# GIP-SIM900.net
KiCad netlist of a schematic drawn in EAGLE
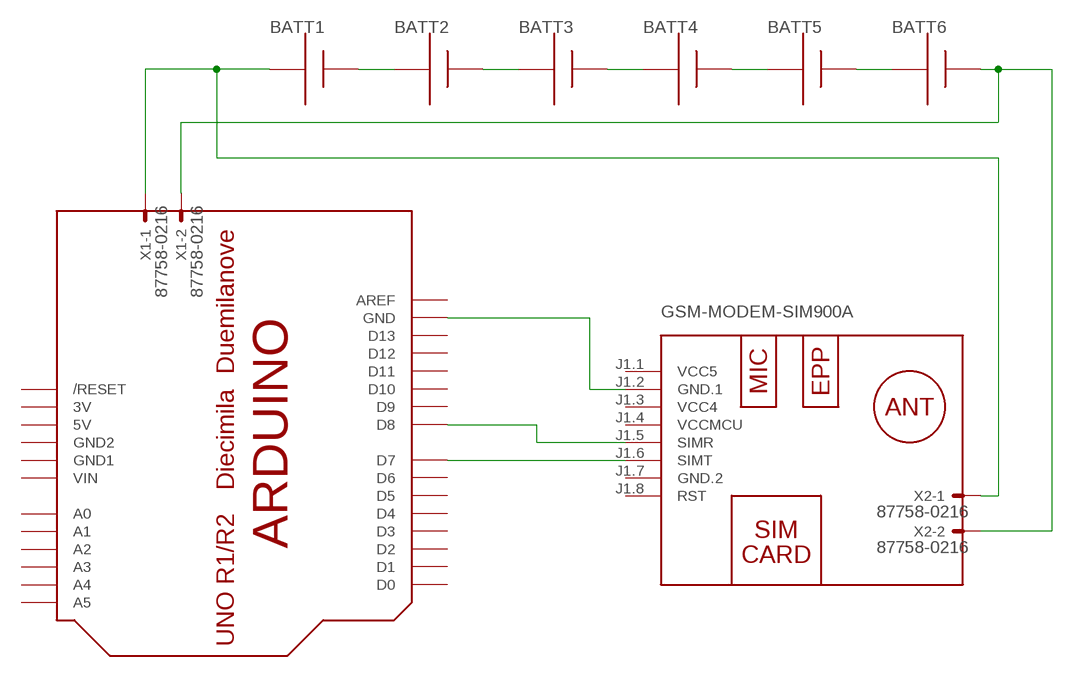
[diagram p0: schematic, sheet 1]

(export (version "E")
  (design (tool "Eeschema 10.0.6"))
  (components
    (comp (ref "BATT1")
      (value "AAA")
      (footprint "eagle-import:12BH412")
      (libsource (lib "eagle-import") (part "AAA"))
    )
    (comp (ref "BATT2")
      (value "AAA")
      (footprint "eagle-import:12BH412")
      (libsource (lib "eagle-import") (part "AAA"))
    )
    (comp (ref "BATT3")
      (value "AAA")
      (footprint "eagle-import:12BH412")
      (libsource (lib "eagle-import") (part "AAA"))
    )
    (comp (ref "BATT4")
      (value "AAA")
      (footprint "eagle-import:12BH412")
      (libsource (lib "eagle-import") (part "AAA"))
    )
    (comp (ref "BATT5")
      (value "AAA")
      (footprint "eagle-import:12BH412")
      (libsource (lib "eagle-import") (part "AAA"))
    )
    (comp (ref "BATT6")
      (value "AAA")
      (footprint "eagle-import:12BH412")
      (libsource (lib "eagle-import") (part "AAA"))
    )
    (comp (ref "U$1")
      (value "GSM-MODEM-SIM900A")
      (footprint "eagle-import:GSM-MODEM-SIM900A")
      (libsource (lib "eagle-import") (part "GSM-MODEM-SIM900A"))
    )
    (comp (ref "U$2")
      (value "ARDUINO-BPLACE")
      (footprint "eagle-import:ARDUINO-BPLACE")
      (libsource (lib "eagle-import") (part "ARDUINO-BPLACE"))
    )
    (comp (ref "X1")
      (value "87758-0216")
      (footprint "eagle-import:87758-0216")
      (fields (field (name "MF") "MOLEX"))
      (libsource (lib "eagle-import") (part "87758-0216"))
    )
    (comp (ref "X2")
      (value "87758-0216")
      (footprint "eagle-import:87758-0216")
      (fields (field (name "MF") "MOLEX"))
      (libsource (lib "eagle-import") (part "87758-0216"))
    )
  )
  (nets
    (net (code "1") (name "/3V") (class "Default")
      (node (ref "U$2") (pin "3V") (pinfunction "3V_3V") (pintype "power_in"))
    )
    (net (code "2") (name "/5V") (class "Default")
      (node (ref "U$2") (pin "5V") (pinfunction "5V_5V") (pintype "power_in"))
    )
    (net (code "3") (name "/GND.2") (class "Default")
      (node (ref "U$1") (pin "J1.7") (pinfunction "GND.2_J1.7") (pintype "power_in"))
    )
    (net (code "4") (name "/GND1") (class "Default")
      (node (ref "U$2") (pin "GND1") (pinfunction "GND1_GND1") (pintype "power_in"))
    )
    (net (code "5") (name "/GND2") (class "Default")
      (node (ref "U$2") (pin "GND2") (pinfunction "GND2_GND2") (pintype "power_in"))
    )
    (net (code "6") (name "/VCC4") (class "Default")
      (node (ref "U$1") (pin "J1.3") (pinfunction "VCC4_J1.3") (pintype "power_in"))
    )
    (net (code "7") (name "/VCC5") (class "Default")
      (node (ref "U$1") (pin "J1.1") (pinfunction "VCC5_J1.1") (pintype "power_in"))
    )
    (net (code "8") (name "/VCCMCU") (class "Default")
      (node (ref "U$1") (pin "J1.4") (pinfunction "VCCMCU_J1.4") (pintype "power_in"))
    )
    (net (code "9") (name "/VIN") (class "Default")
      (node (ref "U$2") (pin "VIN") (pinfunction "VIN_VIN") (pintype "power_in"))
    )
    (net (code "10") (name "Net-(BATT1-Pad+)") (class "Default")
      (node (ref "BATT1") (pin "+") (pinfunction "+_+") (pintype "bidirectional"))
      (node (ref "BATT2") (pin "-") (pinfunction "-_-") (pintype "bidirectional"))
    )
    (net (code "11") (name "Net-(BATT2-Pad+)") (class "Default")
      (node (ref "BATT2") (pin "+") (pinfunction "+_+") (pintype "bidirectional"))
      (node (ref "BATT3") (pin "-") (pinfunction "-_-") (pintype "bidirectional"))
    )
    (net (code "12") (name "Net-(BATT3-Pad+)") (class "Default")
      (node (ref "BATT3") (pin "+") (pinfunction "+_+") (pintype "bidirectional"))
      (node (ref "BATT4") (pin "-") (pinfunction "-_-") (pintype "bidirectional"))
    )
    (net (code "13") (name "Net-(BATT4-Pad+)") (class "Default")
      (node (ref "BATT4") (pin "+") (pinfunction "+_+") (pintype "bidirectional"))
      (node (ref "BATT5") (pin "-") (pinfunction "-_-") (pintype "bidirectional"))
    )
    (net (code "14") (name "Net-(BATT5-Pad+)") (class "Default")
      (node (ref "BATT5") (pin "+") (pinfunction "+_+") (pintype "bidirectional"))
      (node (ref "BATT6") (pin "-") (pinfunction "-_-") (pintype "bidirectional"))
    )
    (net (code "15") (name "Net-(U$1-GND.1)") (class "Default")
      (node (ref "U$1") (pin "J1.2") (pinfunction "GND.1_J1.2") (pintype "power_in"))
      (node (ref "U$2") (pin "GND") (pinfunction "GND_GND") (pintype "power_in"))
    )
    (net (code "16") (name "Net-(U$1-SIMR)") (class "Default")
      (node (ref "U$1") (pin "J1.5") (pinfunction "SIMR_J1.5") (pintype "bidirectional"))
      (node (ref "U$2") (pin "D8") (pinfunction "D8_D8") (pintype "bidirectional"))
    )
    (net (code "17") (name "Net-(U$1-SIMT)") (class "Default")
      (node (ref "U$1") (pin "J1.6") (pinfunction "SIMT_J1.6") (pintype "bidirectional"))
      (node (ref "U$2") (pin "D7") (pinfunction "D7_D7") (pintype "bidirectional"))
    )
    (net (code "18") (name "Net-(X1A-S)") (class "Default")
      (node (ref "BATT1") (pin "-") (pinfunction "-_-") (pintype "bidirectional"))
      (node (ref "X1") (pin "1") (pinfunction "S_1") (pintype "passive"))
      (node (ref "X2") (pin "1") (pinfunction "S_1") (pintype "passive"))
    )
    (net (code "19") (name "Net-(X1B-S)") (class "Default")
      (node (ref "BATT6") (pin "+") (pinfunction "+_+") (pintype "bidirectional"))
      (node (ref "X1") (pin "2") (pinfunction "S_2") (pintype "passive"))
      (node (ref "X2") (pin "2") (pinfunction "S_2") (pintype "passive"))
    )
    (net (code "20") (name "unconnected-(U$1-RST-PadJ1.8)") (class "Default")
      (node (ref "U$1") (pin "J1.8") (pinfunction "RST_J1.8") (pintype "bidirectional"))
    )
    (net (code "21") (name "unconnected-(U$2-PadA0)") (class "Default")
      (node (ref "U$2") (pin "A0") (pinfunction "A0_A0") (pintype "bidirectional"))
    )
    (net (code "22") (name "unconnected-(U$2-PadA1)") (class "Default")
      (node (ref "U$2") (pin "A1") (pinfunction "A1_A1") (pintype "bidirectional"))
    )
    (net (code "23") (name "unconnected-(U$2-PadA2)") (class "Default")
      (node (ref "U$2") (pin "A2") (pinfunction "A2_A2") (pintype "bidirectional"))
    )
    (net (code "24") (name "unconnected-(U$2-PadA3)") (class "Default")
      (node (ref "U$2") (pin "A3") (pinfunction "A3_A3") (pintype "bidirectional"))
    )
    (net (code "25") (name "unconnected-(U$2-PadA4)") (class "Default")
      (node (ref "U$2") (pin "A4") (pinfunction "A4_A4") (pintype "bidirectional"))
    )
    (net (code "26") (name "unconnected-(U$2-PadA5)") (class "Default")
      (node (ref "U$2") (pin "A5") (pinfunction "A5_A5") (pintype "bidirectional"))
    )
    (net (code "27") (name "unconnected-(U$2-PadAREF)") (class "Default")
      (node (ref "U$2") (pin "AREF") (pinfunction "AREF_AREF") (pintype "bidirectional"))
    )
    (net (code "28") (name "unconnected-(U$2-PadD0)") (class "Default")
      (node (ref "U$2") (pin "D0") (pinfunction "D0_D0") (pintype "bidirectional"))
    )
    (net (code "29") (name "unconnected-(U$2-PadD1)") (class "Default")
      (node (ref "U$2") (pin "D1") (pinfunction "D1_D1") (pintype "bidirectional"))
    )
    (net (code "30") (name "unconnected-(U$2-PadD2)") (class "Default")
      (node (ref "U$2") (pin "D2") (pinfunction "D2_D2") (pintype "bidirectional"))
    )
    (net (code "31") (name "unconnected-(U$2-PadD3)") (class "Default")
      (node (ref "U$2") (pin "D3") (pinfunction "D3_D3") (pintype "bidirectional"))
    )
    (net (code "32") (name "unconnected-(U$2-PadD4)") (class "Default")
      (node (ref "U$2") (pin "D4") (pinfunction "D4_D4") (pintype "bidirectional"))
    )
    (net (code "33") (name "unconnected-(U$2-PadD5)") (class "Default")
      (node (ref "U$2") (pin "D5") (pinfunction "D5_D5") (pintype "bidirectional"))
    )
    (net (code "34") (name "unconnected-(U$2-PadD6)") (class "Default")
      (node (ref "U$2") (pin "D6") (pinfunction "D6_D6") (pintype "bidirectional"))
    )
    (net (code "35") (name "unconnected-(U$2-PadD9)") (class "Default")
      (node (ref "U$2") (pin "D9") (pinfunction "D9_D9") (pintype "bidirectional"))
    )
    (net (code "36") (name "unconnected-(U$2-PadD10)") (class "Default")
      (node (ref "U$2") (pin "D10") (pinfunction "D10_D10") (pintype "bidirectional"))
    )
    (net (code "37") (name "unconnected-(U$2-PadD11)") (class "Default")
      (node (ref "U$2") (pin "D11") (pinfunction "D11_D11") (pintype "bidirectional"))
    )
    (net (code "38") (name "unconnected-(U$2-PadD12)") (class "Default")
      (node (ref "U$2") (pin "D12") (pinfunction "D12_D12") (pintype "bidirectional"))
    )
    (net (code "39") (name "unconnected-(U$2-PadD13)") (class "Default")
      (node (ref "U$2") (pin "D13") (pinfunction "D13_D13") (pintype "bidirectional"))
    )
    (net (code "40") (name "unconnected-(U$2-{slash}RESET-PadRESET)") (class "Default")
      (node (ref "U$2") (pin "RESET") (pinfunction "/RESET_RESET") (pintype "bidirectional"))
    )
  )
)
